# Main.net
KiCad netlist of a schematic drawn in Altium Designer
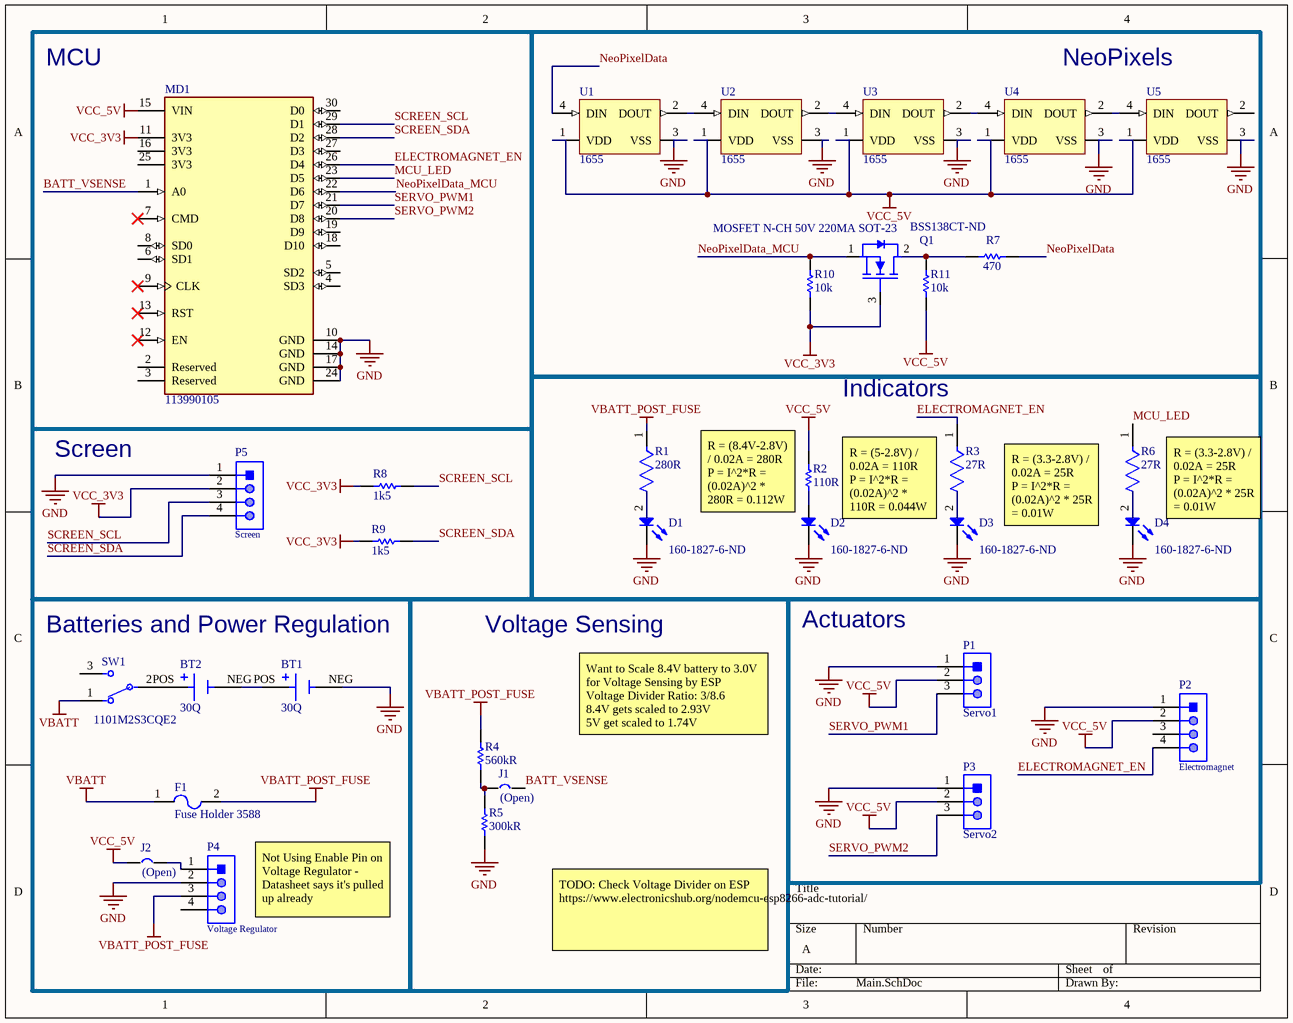
[diagram p0: Main.SchDoc]

(export (version "E")
  (design (tool "Eeschema 10.0.6"))
  (components
    (comp (ref "BT1")
      (value "30Q")
      (footprint "BAT_BK-18650-PC2")
      (description "Battery Holder (Open) 18650 1 Cell PC Pin")
      (fields (field (name "MP") "BK-18650-PC2"))
      (libsource (lib "BK-18650-PC2") (part "BK-18650-PC2"))
    )
    (comp (ref "BT2")
      (value "30Q")
      (footprint "BAT_BK-18650-PC2")
      (description "Battery Holder (Open) 18650 1 Cell PC Pin")
      (fields (field (name "MP") "BK-18650-PC2"))
      (libsource (lib "BK-18650-PC2") (part "BK-18650-PC2"))
    )
    (comp (ref "D1")
      (value "LED BLUE CLEAR CHIP SMD")
      (footprint "DIOC1608X04N")
      (description "Blue 470nm LED Indication - Discrete 2.8V 0603 (1608 Metric)")
      (fields (field (name "SUPPLIER PART NUMBER 1") "160-1827-6-ND"))
      (libsource (lib "CMR_Miscellaneous_Devices") (part "LTST-C193TBKT-5A"))
    )
    (comp (ref "D2")
      (value "LED BLUE CLEAR CHIP SMD")
      (footprint "DIOC1608X04N")
      (description "Blue 470nm LED Indication - Discrete 2.8V 0603 (1608 Metric)")
      (fields (field (name "SUPPLIER PART NUMBER 1") "160-1827-6-ND"))
      (libsource (lib "CMR_Miscellaneous_Devices") (part "LTST-C193TBKT-5A"))
    )
    (comp (ref "D3")
      (value "LED BLUE CLEAR CHIP SMD")
      (footprint "DIOC1608X04N")
      (description "Blue 470nm LED Indication - Discrete 2.8V 0603 (1608 Metric)")
      (fields (field (name "SUPPLIER PART NUMBER 1") "160-1827-6-ND"))
      (libsource (lib "CMR_Miscellaneous_Devices") (part "LTST-C193TBKT-5A"))
    )
    (comp (ref "D4")
      (value "LED BLUE CLEAR CHIP SMD")
      (footprint "DIOC1608X04N")
      (description "Blue 470nm LED Indication - Discrete 2.8V 0603 (1608 Metric)")
      (fields (field (name "SUPPLIER PART NUMBER 1") "160-1827-6-ND"))
      (libsource (lib "CMR_Miscellaneous_Devices") (part "LTST-C193TBKT-5A"))
    )
    (comp (ref "F1")
      (value "Fuse Holder 3588")
      (footprint "Fuse Holder 3588")
      (description "Keystone Electronics 3588")
      (libsource (lib "CMR_Miscellaneous_Devices") (part "3588 Fuse Holder"))
    )
    (comp (ref "J1")
      (value "(Open)")
      (footprint "Solder Jumper")
      (description "Jumper")
      (libsource (lib "CMR_PCB_Components") (part "Jumper"))
    )
    (comp (ref "J2")
      (value "(Open)")
      (footprint "Solder Jumper")
      (description "Jumper")
      (libsource (lib "CMR_PCB_Components") (part "Jumper"))
    )
    (comp (ref "MD1")
      (value "113990105")
      (footprint "FP-113990105-MFG")
      (description "NODEMCU V2 LUA BASED ESP8266 DEV")
      (libsource (lib "Altium Content Vault") (part "b506385fafe4270c41d4fb99a1b6095"))
    )
    (comp (ref "P1")
      (value "Servo1")
      (footprint "MOLX-22-28-4033_V")
      (description "Male Header, Pitch 2.54 mm, 1 x 3 Position, Height 8.38 mm, Tail Length 3.18 mm, RoHS, Bulk")
      (fields (field (name "MANUFACTURER") "Molex"))
      (libsource (lib "Altium Content Vault") (part "CN-1P-M-R3"))
    )
    (comp (ref "P2")
      (value "Electromagnet")
      (footprint "61300411121")
      (description "THT Vertical Pin Header WR-PHD, Pitch 2.54 mm, Single Row, 4 pins")
      (fields
        (field (name "MANUFACTURER") "Wurth Elektronik")
        (field (name "PART NUMBER") "61300411121")
        (field (name "PUBLISHER") "WurthElektronik")
      )
      (libsource (lib "Altium Content Vault") (part "WE-CN-1P-M-R4"))
    )
    (comp (ref "P3")
      (value "Servo2")
      (footprint "MOLX-22-28-4033_V")
      (description "Male Header, Pitch 2.54 mm, 1 x 3 Position, Height 8.38 mm, Tail Length 3.18 mm, RoHS, Bulk")
      (fields (field (name "MANUFACTURER") "Molex"))
      (libsource (lib "Altium Content Vault") (part "CN-1P-M-R3"))
    )
    (comp (ref "P4")
      (value "Voltage Regulator")
      (footprint "61300411121")
      (description "THT Vertical Pin Header WR-PHD, Pitch 2.54 mm, Single Row, 4 pins")
      (fields
        (field (name "MANUFACTURER") "Wurth Elektronik")
        (field (name "PART NUMBER") "61300411121")
        (field (name "PUBLISHER") "WurthElektronik")
      )
      (libsource (lib "Altium Content Vault") (part "WE-CN-1P-M-R4"))
    )
    (comp (ref "P5")
      (value "Screen")
      (footprint "61300411121")
      (description "THT Vertical Pin Header WR-PHD, Pitch 2.54 mm, Single Row, 4 pins")
      (fields
        (field (name "MANUFACTURER") "Wurth Elektronik")
        (field (name "PART NUMBER") "61300411121")
        (field (name "PUBLISHER") "WurthElektronik")
      )
      (libsource (lib "Altium Content Vault") (part "WE-CN-1P-M-R4"))
    )
    (comp (ref "Q1")
      (value "MOSFET N-CH 50V 220MA SOT-23")
      (footprint "SOT90P240X110-3N")
      (description "N-Channel 220mA (Ta) 360mW (Ta) Surface Mount SOT-23-3")
      (fields (field (name "SUPPLIER PART NUMBER 1") "BSS138CT-ND"))
      (libsource (lib "CMR_ICs") (part "BSS138 Fairchild"))
    )
    (comp (ref "R1")
      (value "280R")
      (footprint "FP-RP73P-1J-MFG")
      (description "RES SMD 280 OHM 0.1% 1/6W 0603")
      (fields
        (field (name "MANUFACTURER PART NUMBER") "RP73PF1J280RBTDF")
        (field (name "MANUFACTURER") "TE Connectivity")
      )
      (libsource (lib "Altium Content Vault") (part "1029c3af85768c4190bb7ad29bc67b5"))
    )
    (comp (ref "R2")
      (value "110R")
      (footprint "RESC1609X50X30NL10T20")
      (fields (field (name "PART NUMBER") "CRCW0603110RFKEA") (field (name "MANUFACTURER") "Vishay Dale"))
      (libsource (lib "Altium Content Vault") (part "RES"))
    )
    (comp (ref "R3")
      (value "27R")
      (footprint "FP-ERJ3EK-MFG")
      (description "RES SMD 27 OHM 1% 1/10W 0603")
      (fields (field (name "TOLERANCE") "1%"))
      (libsource (lib "Altium Content Vault") (part "1029c3af85768c4190bb7ad29bc67b5"))
    )
    (comp (ref "R4")
      (value "560kR")
      (footprint "RESC1608X55X30NL15T15")
      (fields (field (name "MANUFACTURER") "Panasonic") (field (name "PART NUMBER") "ERJ3EKF5603V"))
      (libsource (lib "Altium Content Vault") (part "RES"))
    )
    (comp (ref "R5")
      (value "300kR")
      (footprint "RESC1608X55X30ML15T15")
      (fields (field (name "PART NUMBER") "ERJ-3EKF3003V") (field (name "MANUFACTURER") "Panasonic"))
      (libsource (lib "Altium Content Vault") (part "RES"))
    )
    (comp (ref "R6")
      (value "27R")
      (footprint "FP-ERJ3EK-MFG")
      (description "RES SMD 27 OHM 1% 1/10W 0603")
      (fields (field (name "TOLERANCE") "1%"))
      (libsource (lib "Altium Content Vault") (part "1029c3af85768c4190bb7ad29bc67b5"))
    )
    (comp (ref "R7")
      (value "470")
      (footprint "RESC1608X55X30ML15T15")
      (fields (field (name "MANUFACTURER") "Panasonic") (field (name "PART NUMBER") "ERJ-3EKF3001V"))
      (libsource (lib "Altium Content Vault") (part "RES"))
    )
    (comp (ref "R8")
      (value "1k5")
      (footprint "RESC1608X55X25NL10T15")
      (description "Chip Resistor, 5.6 KOhm, +/- 1%, 0.1 W, -55 to 155 degC, 0603 (1608 Metric), RoHS, Tape and Reel")
      (fields (field (name "TOLERANCE") "1%"))
      (libsource (lib "Altium Content Vault") (part "RES-2"))
    )
    (comp (ref "R9")
      (value "1k5")
      (footprint "RESC1608X55X25NL10T15")
      (description "Chip Resistor, 5.6 KOhm, +/- 1%, 0.1 W, -55 to 155 degC, 0603 (1608 Metric), RoHS, Tape and Reel")
      (fields (field (name "TOLERANCE") "1%"))
      (libsource (lib "Altium Content Vault") (part "RES-2"))
    )
    (comp (ref "R10")
      (value "10k")
      (footprint "RESC1608X55X30ML15T15")
      (fields (field (name "MANUFACTURER") "Panasonic") (field (name "PART NUMBER") "ERJ-3EKF3001V"))
      (libsource (lib "Altium Content Vault") (part "RES"))
    )
    (comp (ref "R11")
      (value "10k")
      (footprint "RESC1608X55X30ML15T15")
      (fields (field (name "MANUFACTURER") "Panasonic") (field (name "PART NUMBER") "ERJ-3EKF3001V"))
      (libsource (lib "Altium Content Vault") (part "RES"))
    )
    (comp (ref "SW1")
      (value "1101M2S3CQE2")
      (footprint "FP-1101M2S3CQE2-MFG")
      (description "SWITCH SLIDE SPDT 6A 120V")
      (libsource (lib "Altium Content Vault") (part "7fcaa069a19c2acd609832313418d7c"))
    )
    (comp (ref "U1")
      (value "1655")
      (footprint "ADA-RGB-1655_V")
      (fields (field (name "MANUFACTURER") "Adafruit-Industries-LLC"))
      (libsource (lib "Altium Content Vault") (part "ADA-RGB-1655-4"))
    )
    (comp (ref "U2")
      (value "1655")
      (footprint "ADA-RGB-1655_V")
      (fields (field (name "MANUFACTURER") "Adafruit-Industries-LLC"))
      (libsource (lib "Altium Content Vault") (part "ADA-RGB-1655-4"))
    )
    (comp (ref "U3")
      (value "1655")
      (footprint "ADA-RGB-1655_V")
      (fields (field (name "MANUFACTURER") "Adafruit-Industries-LLC"))
      (libsource (lib "Altium Content Vault") (part "ADA-RGB-1655-4"))
    )
    (comp (ref "U4")
      (value "1655")
      (footprint "ADA-RGB-1655_V")
      (fields (field (name "MANUFACTURER") "Adafruit-Industries-LLC"))
      (libsource (lib "Altium Content Vault") (part "ADA-RGB-1655-4"))
    )
    (comp (ref "U5")
      (value "1655")
      (footprint "ADA-RGB-1655_V")
      (fields (field (name "MANUFACTURER") "Adafruit-Industries-LLC"))
      (libsource (lib "Altium Content Vault") (part "ADA-RGB-1655-4"))
    )
  )
  (nets
    (net (code "1") (name "/BATT_VSENSE") (class "Default")
      (node (ref "J1") (pin "2") (pinfunction "2_2") (pintype "passive"))
      (node (ref "MD1") (pin "1") (pinfunction "A0_1") (pintype "input"))
    )
    (net (code "2") (name "/ELECTROMAGNET_EN") (class "Default")
      (node (ref "MD1") (pin "26") (pinfunction "D4_26") (pintype "bidirectional"))
      (node (ref "P2") (pin "4") (pinfunction "4_4") (pintype "passive"))
      (node (ref "R3") (pin "1") (pinfunction "1_1") (pintype "passive"))
    )
    (net (code "3") (name "/MCU_LED") (class "Default")
      (node (ref "MD1") (pin "23") (pinfunction "D5_23") (pintype "bidirectional"))
      (node (ref "R6") (pin "1") (pinfunction "1_1") (pintype "passive"))
    )
    (net (code "4") (name "/NeoPixelData") (class "Default")
      (node (ref "R7") (pin "1") (pinfunction "1_1") (pintype "passive"))
      (node (ref "U1") (pin "4") (pinfunction "DIN_4") (pintype "input"))
    )
    (net (code "5") (name "/NeoPixelData_MCU") (class "Default")
      (node (ref "MD1") (pin "22") (pinfunction "D6_22") (pintype "bidirectional"))
      (node (ref "Q1") (pin "1") (pinfunction "D_1") (pintype "passive"))
      (node (ref "R10") (pin "1") (pinfunction "1_1") (pintype "passive"))
    )
    (net (code "6") (name "/SCREEN_SCL") (class "Default")
      (node (ref "MD1") (pin "29") (pinfunction "D1_29") (pintype "bidirectional"))
      (node (ref "P5") (pin "3") (pinfunction "3_3") (pintype "passive"))
      (node (ref "R8") (pin "1") (pinfunction "1_1") (pintype "passive"))
    )
    (net (code "7") (name "/SCREEN_SDA") (class "Default")
      (node (ref "MD1") (pin "28") (pinfunction "D2_28") (pintype "bidirectional"))
      (node (ref "P5") (pin "4") (pinfunction "4_4") (pintype "passive"))
      (node (ref "R9") (pin "1") (pinfunction "1_1") (pintype "passive"))
    )
    (net (code "8") (name "/SERVO_PWM1") (class "Default")
      (node (ref "MD1") (pin "21") (pinfunction "D7_21") (pintype "bidirectional"))
      (node (ref "P1") (pin "3") (pinfunction "3_3") (pintype "passive"))
    )
    (net (code "9") (name "/SERVO_PWM2") (class "Default")
      (node (ref "MD1") (pin "20") (pinfunction "D8_20") (pintype "bidirectional"))
      (node (ref "P3") (pin "3") (pinfunction "3_3") (pintype "passive"))
    )
    (net (code "10") (name "GND") (class "Default")
      (node (ref "BT1") (pin "NEG") (pinfunction "NEG_NEG") (pintype "passive"))
      (node (ref "D1") (pin "1") (pinfunction "K_1") (pintype "passive"))
      (node (ref "D2") (pin "1") (pinfunction "K_1") (pintype "passive"))
      (node (ref "D3") (pin "1") (pinfunction "K_1") (pintype "passive"))
      (node (ref "D4") (pin "1") (pinfunction "K_1") (pintype "passive"))
      (node (ref "MD1") (pin "10") (pinfunction "GND_10") (pintype "power_in"))
      (node (ref "MD1") (pin "14") (pinfunction "GND_14") (pintype "power_in"))
      (node (ref "MD1") (pin "17") (pinfunction "GND_17") (pintype "power_in"))
      (node (ref "MD1") (pin "24") (pinfunction "GND_24") (pintype "power_in"))
      (node (ref "P1") (pin "1") (pinfunction "1_1") (pintype "passive"))
      (node (ref "P2") (pin "1") (pinfunction "1_1") (pintype "passive"))
      (node (ref "P3") (pin "1") (pinfunction "1_1") (pintype "passive"))
      (node (ref "P4") (pin "2") (pinfunction "2_2") (pintype "passive"))
      (node (ref "P5") (pin "1") (pinfunction "1_1") (pintype "passive"))
      (node (ref "R5") (pin "1") (pinfunction "1_1") (pintype "passive"))
      (node (ref "U1") (pin "3") (pinfunction "VSS_3") (pintype "power_in"))
      (node (ref "U2") (pin "3") (pinfunction "VSS_3") (pintype "power_in"))
      (node (ref "U3") (pin "3") (pinfunction "VSS_3") (pintype "power_in"))
      (node (ref "U4") (pin "3") (pinfunction "VSS_3") (pintype "power_in"))
      (node (ref "U5") (pin "3") (pinfunction "VSS_3") (pintype "power_in"))
    )
    (net (code "11") (name "Net-(BT1-PadPOS)") (class "Default")
      (node (ref "BT1") (pin "POS") (pinfunction "POS_POS") (pintype "passive"))
      (node (ref "BT2") (pin "NEG") (pinfunction "NEG_NEG") (pintype "passive"))
    )
    (net (code "12") (name "Net-(D1-A)") (class "Default")
      (node (ref "D1") (pin "2") (pinfunction "A_2") (pintype "passive"))
      (node (ref "R1") (pin "2") (pinfunction "2_2") (pintype "passive"))
    )
    (net (code "13") (name "Net-(D2-A)") (class "Default")
      (node (ref "D2") (pin "2") (pinfunction "A_2") (pintype "passive"))
      (node (ref "R2") (pin "1") (pinfunction "1_1") (pintype "passive"))
    )
    (net (code "14") (name "Net-(D3-A)") (class "Default")
      (node (ref "D3") (pin "2") (pinfunction "A_2") (pintype "passive"))
      (node (ref "R3") (pin "2") (pinfunction "2_2") (pintype "passive"))
    )
    (net (code "15") (name "Net-(D4-A)") (class "Default")
      (node (ref "D4") (pin "2") (pinfunction "A_2") (pintype "passive"))
      (node (ref "R6") (pin "2") (pinfunction "2_2") (pintype "passive"))
    )
    (net (code "16") (name "Net-(J1-Pad1)") (class "Default")
      (node (ref "J1") (pin "1") (pinfunction "1_1") (pintype "passive"))
      (node (ref "R4") (pin "1") (pinfunction "1_1") (pintype "passive"))
      (node (ref "R5") (pin "2") (pinfunction "2_2") (pintype "passive"))
    )
    (net (code "17") (name "Net-(J2-Pad2)") (class "Default")
      (node (ref "J2") (pin "2") (pinfunction "2_2") (pintype "passive"))
      (node (ref "P4") (pin "1") (pinfunction "1_1") (pintype "passive"))
    )
    (net (code "18") (name "Net-(Q1-S)") (class "Default")
      (node (ref "Q1") (pin "2") (pinfunction "S_2") (pintype "passive"))
      (node (ref "R11") (pin "1") (pinfunction "1_1") (pintype "passive"))
      (node (ref "R7") (pin "2") (pinfunction "2_2") (pintype "passive"))
    )
    (net (code "19") (name "Net-(SW1-COMM)") (class "Default")
      (node (ref "BT2") (pin "POS") (pinfunction "POS_POS") (pintype "passive"))
      (node (ref "SW1") (pin "2") (pinfunction "COMM_2") (pintype "passive"))
    )
    (net (code "20") (name "Net-(U1-DOUT)") (class "Default")
      (node (ref "U1") (pin "2") (pinfunction "DOUT_2") (pintype "output"))
      (node (ref "U2") (pin "4") (pinfunction "DIN_4") (pintype "input"))
    )
    (net (code "21") (name "Net-(U2-DOUT)") (class "Default")
      (node (ref "U2") (pin "2") (pinfunction "DOUT_2") (pintype "output"))
      (node (ref "U3") (pin "4") (pinfunction "DIN_4") (pintype "input"))
    )
    (net (code "22") (name "Net-(U3-DOUT)") (class "Default")
      (node (ref "U3") (pin "2") (pinfunction "DOUT_2") (pintype "output"))
      (node (ref "U4") (pin "4") (pinfunction "DIN_4") (pintype "input"))
    )
    (net (code "23") (name "Net-(U4-DOUT)") (class "Default")
      (node (ref "U4") (pin "2") (pinfunction "DOUT_2") (pintype "output"))
      (node (ref "U5") (pin "4") (pinfunction "DIN_4") (pintype "input"))
    )
    (net (code "24") (name "VBATT") (class "Default")
      (node (ref "F1") (pin "1") (pinfunction "1_1") (pintype "passive"))
      (node (ref "SW1") (pin "1") (pinfunction "1_1") (pintype "passive"))
    )
    (net (code "25") (name "VBATT_POST_FUSE") (class "Default")
      (node (ref "F1") (pin "2") (pinfunction "2_2") (pintype "passive"))
      (node (ref "P4") (pin "3") (pinfunction "3_3") (pintype "passive"))
      (node (ref "R1") (pin "1") (pinfunction "1_1") (pintype "passive"))
      (node (ref "R4") (pin "2") (pinfunction "2_2") (pintype "passive"))
    )
    (net (code "26") (name "VCC_3V3") (class "Default")
      (node (ref "MD1") (pin "11") (pinfunction "3V3_11") (pintype "power_in"))
      (node (ref "P5") (pin "2") (pinfunction "2_2") (pintype "passive"))
      (node (ref "Q1") (pin "3") (pinfunction "G_3") (pintype "passive"))
      (node (ref "R10") (pin "2") (pinfunction "2_2") (pintype "passive"))
      (node (ref "R8") (pin "2") (pinfunction "2_2") (pintype "passive"))
      (node (ref "R9") (pin "2") (pinfunction "2_2") (pintype "passive"))
    )
    (net (code "27") (name "VCC_5V") (class "Default")
      (node (ref "J2") (pin "1") (pinfunction "1_1") (pintype "passive"))
      (node (ref "MD1") (pin "15") (pinfunction "VIN_15") (pintype "power_in"))
      (node (ref "P1") (pin "2") (pinfunction "2_2") (pintype "passive"))
      (node (ref "P2") (pin "2") (pinfunction "2_2") (pintype "passive"))
      (node (ref "P3") (pin "2") (pinfunction "2_2") (pintype "passive"))
      (node (ref "R11") (pin "2") (pinfunction "2_2") (pintype "passive"))
      (node (ref "R2") (pin "2") (pinfunction "2_2") (pintype "passive"))
      (node (ref "U1") (pin "1") (pinfunction "VDD_1") (pintype "power_in"))
      (node (ref "U2") (pin "1") (pinfunction "VDD_1") (pintype "power_in"))
      (node (ref "U3") (pin "1") (pinfunction "VDD_1") (pintype "power_in"))
      (node (ref "U4") (pin "1") (pinfunction "VDD_1") (pintype "power_in"))
      (node (ref "U5") (pin "1") (pinfunction "VDD_1") (pintype "power_in"))
    )
    (net (code "28") (name "unconnected-(MD1-3V3-Pad16)") (class "Default")
      (node (ref "MD1") (pin "16") (pinfunction "3V3_16") (pintype "power_in"))
    )
    (net (code "29") (name "unconnected-(MD1-3V3-Pad25)") (class "Default")
      (node (ref "MD1") (pin "25") (pinfunction "3V3_25") (pintype "power_in"))
    )
    (net (code "30") (name "unconnected-(MD1-CLK-Pad9)") (class "Default")
      (node (ref "MD1") (pin "9") (pinfunction "CLK_9") (pintype "input+no_connect"))
    )
    (net (code "31") (name "unconnected-(MD1-CMD-Pad7)") (class "Default")
      (node (ref "MD1") (pin "7") (pinfunction "CMD_7") (pintype "input+no_connect"))
    )
    (net (code "32") (name "unconnected-(MD1-D0-Pad30)") (class "Default")
      (node (ref "MD1") (pin "30") (pinfunction "D0_30") (pintype "bidirectional"))
    )
    (net (code "33") (name "unconnected-(MD1-D3-Pad27)") (class "Default")
      (node (ref "MD1") (pin "27") (pinfunction "D3_27") (pintype "bidirectional"))
    )
    (net (code "34") (name "unconnected-(MD1-D9-Pad19)") (class "Default")
      (node (ref "MD1") (pin "19") (pinfunction "D9_19") (pintype "bidirectional"))
    )
    (net (code "35") (name "unconnected-(MD1-D10-Pad18)") (class "Default")
      (node (ref "MD1") (pin "18") (pinfunction "D10_18") (pintype "bidirectional"))
    )
    (net (code "36") (name "unconnected-(MD1-EN-Pad12)") (class "Default")
      (node (ref "MD1") (pin "12") (pinfunction "EN_12") (pintype "input+no_connect"))
    )
    (net (code "37") (name "unconnected-(MD1-RST-Pad13)") (class "Default")
      (node (ref "MD1") (pin "13") (pinfunction "RST_13") (pintype "input+no_connect"))
    )
    (net (code "38") (name "unconnected-(MD1-Reserved-Pad2)") (class "Default")
      (node (ref "MD1") (pin "2") (pinfunction "Reserved_2") (pintype "passive"))
    )
    (net (code "39") (name "unconnected-(MD1-Reserved-Pad3)") (class "Default")
      (node (ref "MD1") (pin "3") (pinfunction "Reserved_3") (pintype "passive"))
    )
    (net (code "40") (name "unconnected-(MD1-SD0-Pad8)") (class "Default")
      (node (ref "MD1") (pin "8") (pinfunction "SD0_8") (pintype "bidirectional"))
    )
    (net (code "41") (name "unconnected-(MD1-SD1-Pad6)") (class "Default")
      (node (ref "MD1") (pin "6") (pinfunction "SD1_6") (pintype "bidirectional"))
    )
    (net (code "42") (name "unconnected-(MD1-SD2-Pad5)") (class "Default")
      (node (ref "MD1") (pin "5") (pinfunction "SD2_5") (pintype "bidirectional"))
    )
    (net (code "43") (name "unconnected-(MD1-SD3-Pad4)") (class "Default")
      (node (ref "MD1") (pin "4") (pinfunction "SD3_4") (pintype "bidirectional"))
    )
    (net (code "44") (name "unconnected-(P2-Pad3)") (class "Default")
      (node (ref "P2") (pin "3") (pinfunction "3_3") (pintype "passive"))
    )
    (net (code "45") (name "unconnected-(P4-Pad4)") (class "Default")
      (node (ref "P4") (pin "4") (pinfunction "4_4") (pintype "passive"))
    )
    (net (code "46") (name "unconnected-(SW1-Pad3)") (class "Default")
      (node (ref "SW1") (pin "3") (pinfunction "3_3") (pintype "passive"))
    )
    (net (code "47") (name "unconnected-(U5-DOUT-Pad2)") (class "Default")
      (node (ref "U5") (pin "2") (pinfunction "DOUT_2") (pintype "output"))
    )
  )
)
